# thunder.net
KiCad netlist of a schematic drawn in EAGLE
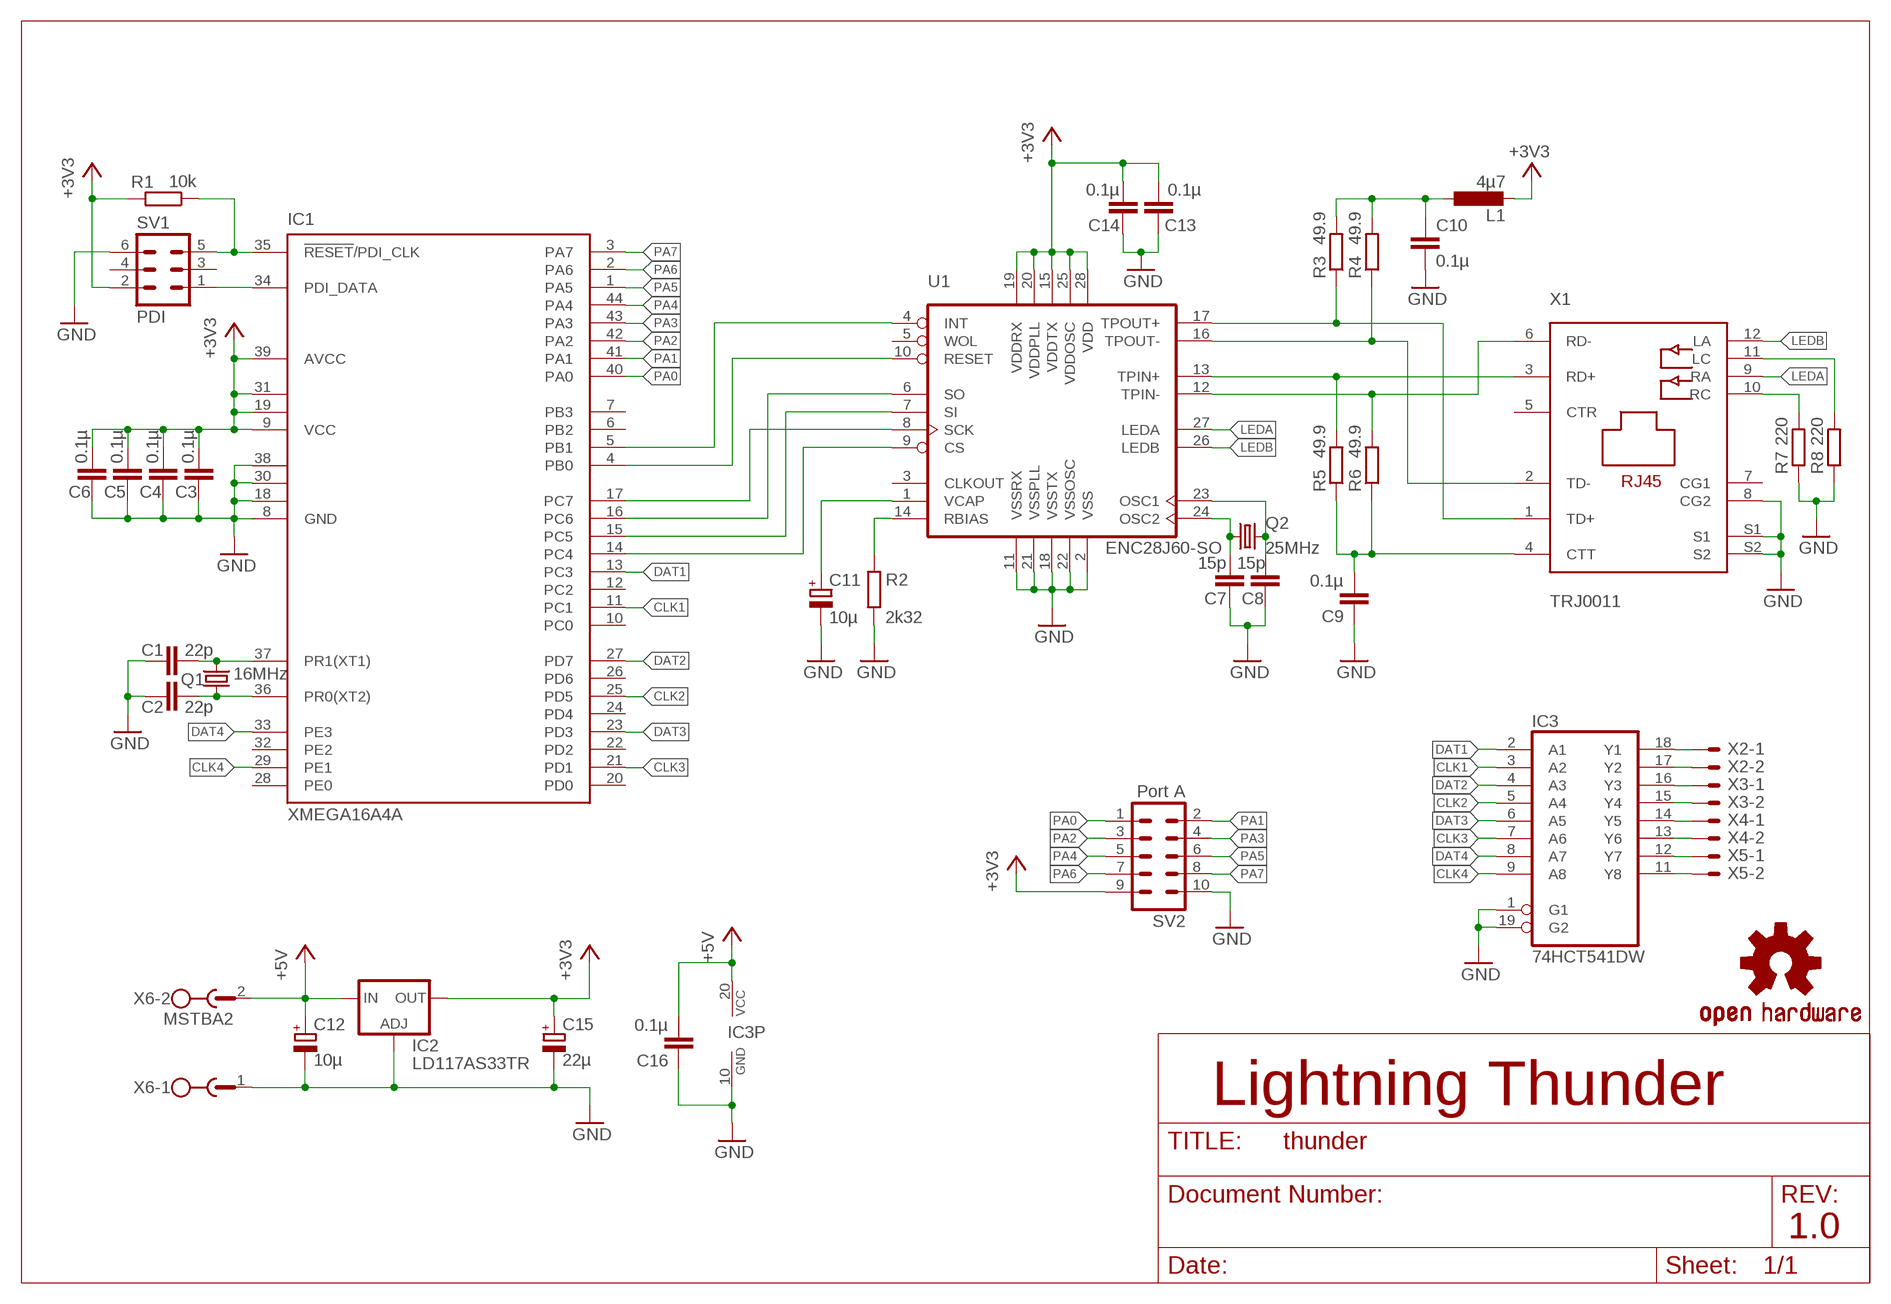
[diagram p0: schematic, sheet 1]

(export (version "E")
  (design (tool "Eeschema 10.0.6"))
  (components
    (comp (ref "C1")
      (value "22p")
      (footprint "eagle-import:C0805")
      (libsource (lib "eagle-import") (part "C-EUC0805"))
    )
    (comp (ref "C2")
      (value "22p")
      (footprint "eagle-import:C0805")
      (libsource (lib "eagle-import") (part "C-EUC0805"))
    )
    (comp (ref "C3")
      (value "0.1µ")
      (footprint "eagle-import:C0805")
      (libsource (lib "eagle-import") (part "C-EUC0805"))
    )
    (comp (ref "C4")
      (value "0.1µ")
      (footprint "eagle-import:C0805")
      (libsource (lib "eagle-import") (part "C-EUC0805"))
    )
    (comp (ref "C5")
      (value "0.1µ")
      (footprint "eagle-import:C0805")
      (libsource (lib "eagle-import") (part "C-EUC0805"))
    )
    (comp (ref "C6")
      (value "0.1µ")
      (footprint "eagle-import:C0805")
      (libsource (lib "eagle-import") (part "C-EUC0805"))
    )
    (comp (ref "C7")
      (value "15p")
      (footprint "eagle-import:C0805")
      (libsource (lib "eagle-import") (part "C-EUC0805"))
    )
    (comp (ref "C8")
      (value "15p")
      (footprint "eagle-import:C0805")
      (libsource (lib "eagle-import") (part "C-EUC0805"))
    )
    (comp (ref "C9")
      (value "0.1µ")
      (footprint "eagle-import:C0805")
      (libsource (lib "eagle-import") (part "C-EUC0805"))
    )
    (comp (ref "C10")
      (value "0.1µ")
      (footprint "eagle-import:C0805")
      (libsource (lib "eagle-import") (part "C-EUC0805"))
    )
    (comp (ref "C11")
      (value "10µ")
      (footprint "eagle-import:B_3528-21R")
      (libsource (lib "eagle-import") (part "CPOL-EUB/3528-21R"))
    )
    (comp (ref "C12")
      (value "10µ")
      (footprint "eagle-import:B_3528-21R")
      (libsource (lib "eagle-import") (part "CPOL-EUB/3528-21R"))
    )
    (comp (ref "C13")
      (value "0.1µ")
      (footprint "eagle-import:C0805")
      (libsource (lib "eagle-import") (part "C-EUC0805"))
    )
    (comp (ref "C14")
      (value "0.1µ")
      (footprint "eagle-import:C0805")
      (libsource (lib "eagle-import") (part "C-EUC0805"))
    )
    (comp (ref "C15")
      (value "22µ")
      (footprint "eagle-import:B_3528-21R")
      (libsource (lib "eagle-import") (part "CPOL-EUB/3528-21R"))
    )
    (comp (ref "C16")
      (value "0.1µ")
      (footprint "eagle-import:C0805")
      (libsource (lib "eagle-import") (part "C-EUC0805"))
    )
    (comp (ref "IC1")
      (value "XMEGA16A4A")
      (footprint "eagle-import:TQFP44")
      (libsource (lib "eagle-import") (part "XMEGA16A4A"))
    )
    (comp (ref "IC2")
      (value "LD117AS33TR")
      (footprint "eagle-import:SOT223")
      (libsource (lib "eagle-import") (part "LD117A?S33TR"))
    )
    (comp (ref "IC3")
      (value "74HCT541DW")
      (footprint "eagle-import:SO20W")
      (libsource (lib "eagle-import") (part "74541DWHCT"))
    )
    (comp (ref "L1")
      (value "4µ7")
      (footprint "eagle-import:L3225M")
      (libsource (lib "eagle-import") (part "L-EUL3225M"))
    )
    (comp (ref "LOGO1")
      (value "OSHW-LOGOS")
      (footprint "eagle-import:OSHW-LOGO-S")
      (libsource (lib "eagle-import") (part "OSHW-LOGOS"))
    )
    (comp (ref "Q1")
      (value "16MHz")
      (footprint "eagle-import:HC49U-V")
      (libsource (lib "eagle-import") (part "CRYSTALHC49U-V"))
    )
    (comp (ref "Q2")
      (value "25MHz")
      (footprint "eagle-import:HC49U-V")
      (libsource (lib "eagle-import") (part "CRYSTALHC49U-V"))
    )
    (comp (ref "R1")
      (value "10k")
      (footprint "eagle-import:R0805")
      (libsource (lib "eagle-import") (part "R-EU_R0805"))
    )
    (comp (ref "R2")
      (value "2k32")
      (footprint "eagle-import:R0805")
      (libsource (lib "eagle-import") (part "R-EU_R0805"))
    )
    (comp (ref "R3")
      (value "49.9")
      (footprint "eagle-import:R0805")
      (libsource (lib "eagle-import") (part "R-EU_R0805"))
    )
    (comp (ref "R4")
      (value "49.9")
      (footprint "eagle-import:R0805")
      (libsource (lib "eagle-import") (part "R-EU_R0805"))
    )
    (comp (ref "R5")
      (value "49.9")
      (footprint "eagle-import:R0805")
      (libsource (lib "eagle-import") (part "R-EU_R0805"))
    )
    (comp (ref "R6")
      (value "49.9")
      (footprint "eagle-import:R0805")
      (libsource (lib "eagle-import") (part "R-EU_R0805"))
    )
    (comp (ref "R7")
      (value "220")
      (footprint "eagle-import:R0805")
      (libsource (lib "eagle-import") (part "R-EU_R0805"))
    )
    (comp (ref "R8")
      (value "220")
      (footprint "eagle-import:R0805")
      (libsource (lib "eagle-import") (part "R-EU_R0805"))
    )
    (comp (ref "SV1")
      (value "PDI")
      (footprint "eagle-import:ML6")
      (libsource (lib "eagle-import") (part "ML6"))
    )
    (comp (ref "SV2")
      (value "Port A")
      (footprint "eagle-import:MA05-2")
      (libsource (lib "eagle-import") (part "MA05-2"))
    )
    (comp (ref "U1")
      (value "ENC28J60-SO")
      (footprint "eagle-import:SO28W")
      (libsource (lib "eagle-import") (part "ENC28J60-SO"))
    )
    (comp (ref "X1")
      (value "TRJ0011")
      (footprint "eagle-import:TRJ0011")
      (libsource (lib "eagle-import") (part "TRJ0011"))
    )
    (comp (ref "X2")
      (value "AKL18X-02W")
      (footprint "eagle-import:AKL182-02")
      (libsource (lib "eagle-import") (part "AKL18X-02W"))
    )
    (comp (ref "X3")
      (value "AKL18X-02W")
      (footprint "eagle-import:AKL182-02")
      (libsource (lib "eagle-import") (part "AKL18X-02W"))
    )
    (comp (ref "X4")
      (value "AKL18X-02W")
      (footprint "eagle-import:AKL182-02")
      (libsource (lib "eagle-import") (part "AKL18X-02W"))
    )
    (comp (ref "X5")
      (value "AKL18X-02W")
      (footprint "eagle-import:AKL182-02")
      (libsource (lib "eagle-import") (part "AKL18X-02W"))
    )
    (comp (ref "X6")
      (value "MSTBA2")
      (footprint "eagle-import:MSTBA2")
      (fields (field (name "MF") "FARNELL") (field (name "MPN") "1757242"))
      (libsource (lib "eagle-import") (part "MSTBA2"))
    )
  )
  (nets
    (net (code "1") (name "+3V3") (class "Default")
      (node (ref "C13") (pin "2") (pinfunction "2_2") (pintype "passive"))
      (node (ref "C14") (pin "2") (pinfunction "2_2") (pintype "passive"))
      (node (ref "C15") (pin "+") (pinfunction "+_+") (pintype "passive"))
      (node (ref "C3") (pin "2") (pinfunction "2_2") (pintype "passive"))
      (node (ref "C4") (pin "2") (pinfunction "2_2") (pintype "passive"))
      (node (ref "C5") (pin "2") (pinfunction "2_2") (pintype "passive"))
      (node (ref "C6") (pin "2") (pinfunction "2_2") (pintype "passive"))
      (node (ref "IC1") (pin "19") (pinfunction "VCC1_19") (pintype "power_in"))
      (node (ref "IC1") (pin "31") (pinfunction "VCC2_31") (pintype "power_in"))
      (node (ref "IC1") (pin "39") (pinfunction "AVCC_39") (pintype "power_in"))
      (node (ref "IC1") (pin "9") (pinfunction "VCC_9") (pintype "power_in"))
      (node (ref "IC2") (pin "4") (pinfunction "OUT_4") (pintype "passive"))
      (node (ref "L1") (pin "2") (pinfunction "2_2") (pintype "passive"))
      (node (ref "R1") (pin "2") (pinfunction "2_2") (pintype "passive"))
      (node (ref "SV1") (pin "2") (pinfunction "2_2") (pintype "passive"))
      (node (ref "SV2") (pin "9") (pinfunction "9_9") (pintype "passive"))
      (node (ref "U1") (pin "15") (pinfunction "VDDTX_15") (pintype "power_in"))
      (node (ref "U1") (pin "19") (pinfunction "VDDRX_19") (pintype "power_in"))
      (node (ref "U1") (pin "20") (pinfunction "VDDPLL_20") (pintype "power_in"))
      (node (ref "U1") (pin "25") (pinfunction "VDDOSC_25") (pintype "power_in"))
      (node (ref "U1") (pin "28") (pinfunction "VDD_28") (pintype "power_in"))
    )
    (net (code "2") (name "+5V") (class "Default")
      (node (ref "C12") (pin "+") (pinfunction "+_+") (pintype "passive"))
      (node (ref "C16") (pin "2") (pinfunction "2_2") (pintype "passive"))
      (node (ref "IC2") (pin "3") (pinfunction "IN_3") (pintype "input"))
      (node (ref "IC3") (pin "20") (pinfunction "VCC_20") (pintype "power_in"))
      (node (ref "X6") (pin "2") (pinfunction "1_2") (pintype "passive"))
    )
    (net (code "3") (name "CLK1") (class "Default")
      (node (ref "IC1") (pin "11") (pinfunction "PC1_11") (pintype "bidirectional"))
      (node (ref "IC3") (pin "3") (pinfunction "A2_3") (pintype "input"))
    )
    (net (code "4") (name "CLK2") (class "Default")
      (node (ref "IC1") (pin "25") (pinfunction "PD5_25") (pintype "bidirectional"))
      (node (ref "IC3") (pin "5") (pinfunction "A4_5") (pintype "input"))
    )
    (net (code "5") (name "CLK3") (class "Default")
      (node (ref "IC1") (pin "21") (pinfunction "PD1_21") (pintype "bidirectional"))
      (node (ref "IC3") (pin "7") (pinfunction "A6_7") (pintype "input"))
    )
    (net (code "6") (name "CLK4") (class "Default")
      (node (ref "IC1") (pin "29") (pinfunction "PE1_29") (pintype "bidirectional"))
      (node (ref "IC3") (pin "9") (pinfunction "A8_9") (pintype "input"))
    )
    (net (code "7") (name "DAT1") (class "Default")
      (node (ref "IC1") (pin "13") (pinfunction "PC3_13") (pintype "bidirectional"))
      (node (ref "IC3") (pin "2") (pinfunction "A1_2") (pintype "input"))
    )
    (net (code "8") (name "DAT2") (class "Default")
      (node (ref "IC1") (pin "27") (pinfunction "PD7_27") (pintype "bidirectional"))
      (node (ref "IC3") (pin "4") (pinfunction "A3_4") (pintype "input"))
    )
    (net (code "9") (name "DAT3") (class "Default")
      (node (ref "IC1") (pin "23") (pinfunction "PD3_23") (pintype "bidirectional"))
      (node (ref "IC3") (pin "6") (pinfunction "A5_6") (pintype "input"))
    )
    (net (code "10") (name "DAT4") (class "Default")
      (node (ref "IC1") (pin "33") (pinfunction "PE3_33") (pintype "bidirectional"))
      (node (ref "IC3") (pin "8") (pinfunction "A7_8") (pintype "input"))
    )
    (net (code "11") (name "GND") (class "Default")
      (node (ref "C1") (pin "1") (pinfunction "1_1") (pintype "passive"))
      (node (ref "C10") (pin "2") (pinfunction "2_2") (pintype "passive"))
      (node (ref "C11") (pin "-") (pinfunction "-_-") (pintype "passive"))
      (node (ref "C12") (pin "-") (pinfunction "-_-") (pintype "passive"))
      (node (ref "C13") (pin "1") (pinfunction "1_1") (pintype "passive"))
      (node (ref "C14") (pin "1") (pinfunction "1_1") (pintype "passive"))
      (node (ref "C15") (pin "-") (pinfunction "-_-") (pintype "passive"))
      (node (ref "C16") (pin "1") (pinfunction "1_1") (pintype "passive"))
      (node (ref "C2") (pin "1") (pinfunction "1_1") (pintype "passive"))
      (node (ref "C3") (pin "1") (pinfunction "1_1") (pintype "passive"))
      (node (ref "C4") (pin "1") (pinfunction "1_1") (pintype "passive"))
      (node (ref "C5") (pin "1") (pinfunction "1_1") (pintype "passive"))
      (node (ref "C6") (pin "1") (pinfunction "1_1") (pintype "passive"))
      (node (ref "C7") (pin "1") (pinfunction "1_1") (pintype "passive"))
      (node (ref "C8") (pin "1") (pinfunction "1_1") (pintype "passive"))
      (node (ref "C9") (pin "1") (pinfunction "1_1") (pintype "passive"))
      (node (ref "IC1") (pin "18") (pinfunction "GND1_18") (pintype "power_in"))
      (node (ref "IC1") (pin "30") (pinfunction "GND2_30") (pintype "power_in"))
      (node (ref "IC1") (pin "38") (pinfunction "GND3_38") (pintype "power_in"))
      (node (ref "IC1") (pin "8") (pinfunction "GND_8") (pintype "power_in"))
      (node (ref "IC2") (pin "1") (pinfunction "ADJ_1") (pintype "input"))
      (node (ref "IC3") (pin "1") (pinfunction "G1_1") (pintype "input"))
      (node (ref "IC3") (pin "10") (pinfunction "GND_10") (pintype "power_in"))
      (node (ref "IC3") (pin "19") (pinfunction "G2_19") (pintype "input"))
      (node (ref "R2") (pin "1") (pinfunction "1_1") (pintype "passive"))
      (node (ref "R7") (pin "1") (pinfunction "1_1") (pintype "passive"))
      (node (ref "R8") (pin "1") (pinfunction "1_1") (pintype "passive"))
      (node (ref "SV1") (pin "6") (pinfunction "6_6") (pintype "passive"))
      (node (ref "SV2") (pin "10") (pinfunction "10_10") (pintype "passive"))
      (node (ref "U1") (pin "11") (pinfunction "VSSRX_11") (pintype "power_in"))
      (node (ref "U1") (pin "18") (pinfunction "VSSTX_18") (pintype "power_in"))
      (node (ref "U1") (pin "2") (pinfunction "VSS_2") (pintype "power_in"))
      (node (ref "U1") (pin "21") (pinfunction "VSSPLL_21") (pintype "power_in"))
      (node (ref "U1") (pin "22") (pinfunction "VSSOSC_22") (pintype "power_in"))
      (node (ref "X1") (pin "8") (pinfunction "CG2_8") (pintype "passive"))
      (node (ref "X1") (pin "S1") (pinfunction "S1_S1") (pintype "passive"))
      (node (ref "X1") (pin "S2") (pinfunction "S2_S2") (pintype "passive"))
      (node (ref "X6") (pin "1") (pinfunction "1_1") (pintype "passive"))
    )
    (net (code "12") (name "LEDA") (class "Default")
      (node (ref "U1") (pin "27") (pinfunction "LEDA_27") (pintype "output"))
      (node (ref "X1") (pin "9") (pinfunction "RA_9") (pintype "passive"))
    )
    (net (code "13") (name "LEDB") (class "Default")
      (node (ref "U1") (pin "26") (pinfunction "LEDB_26") (pintype "output"))
      (node (ref "X1") (pin "12") (pinfunction "LA_12") (pintype "passive"))
    )
    (net (code "14") (name "Net-(C10-Pad1)") (class "Default")
      (node (ref "C10") (pin "1") (pinfunction "1_1") (pintype "passive"))
      (node (ref "L1") (pin "1") (pinfunction "1_1") (pintype "passive"))
      (node (ref "R3") (pin "2") (pinfunction "2_2") (pintype "passive"))
      (node (ref "R4") (pin "2") (pinfunction "2_2") (pintype "passive"))
    )
    (net (code "15") (name "Net-(IC1-PB0)") (class "Default")
      (node (ref "IC1") (pin "4") (pinfunction "PB0_4") (pintype "bidirectional"))
      (node (ref "U1") (pin "10") (pinfunction "RESET_10") (pintype "input"))
    )
    (net (code "16") (name "Net-(IC1-PB1)") (class "Default")
      (node (ref "IC1") (pin "5") (pinfunction "PB1_5") (pintype "bidirectional"))
      (node (ref "U1") (pin "4") (pinfunction "INT_4") (pintype "output"))
    )
    (net (code "17") (name "Net-(IC1-PC4)") (class "Default")
      (node (ref "IC1") (pin "14") (pinfunction "PC4_14") (pintype "bidirectional"))
      (node (ref "U1") (pin "9") (pinfunction "CS_9") (pintype "input"))
    )
    (net (code "18") (name "Net-(IC1-PC5)") (class "Default")
      (node (ref "IC1") (pin "15") (pinfunction "PC5_15") (pintype "bidirectional"))
      (node (ref "U1") (pin "7") (pinfunction "SI_7") (pintype "input"))
    )
    (net (code "19") (name "Net-(IC1-PC6)") (class "Default")
      (node (ref "IC1") (pin "16") (pinfunction "PC6_16") (pintype "bidirectional"))
      (node (ref "U1") (pin "6") (pinfunction "SO_6") (pintype "open_collector"))
    )
    (net (code "20") (name "Net-(IC1-PC7)") (class "Default")
      (node (ref "IC1") (pin "17") (pinfunction "PC7_17") (pintype "bidirectional"))
      (node (ref "U1") (pin "8") (pinfunction "SCK_8") (pintype "input"))
    )
    (net (code "21") (name "Net-(IC1-PDI_DATA)") (class "Default")
      (node (ref "IC1") (pin "34") (pinfunction "PDI_DATA_34") (pintype "bidirectional"))
      (node (ref "SV1") (pin "1") (pinfunction "1_1") (pintype "passive"))
    )
    (net (code "22") (name "Net-(IC1-PR0(XT2))") (class "Default")
      (node (ref "C2") (pin "2") (pinfunction "2_2") (pintype "passive"))
      (node (ref "IC1") (pin "36") (pinfunction "PR0(XT2)_36") (pintype "bidirectional"))
      (node (ref "Q1") (pin "1") (pinfunction "1_1") (pintype "passive"))
    )
    (net (code "23") (name "Net-(IC1-PR1(XT1))") (class "Default")
      (node (ref "C1") (pin "2") (pinfunction "2_2") (pintype "passive"))
      (node (ref "IC1") (pin "37") (pinfunction "PR1(XT1)_37") (pintype "bidirectional"))
      (node (ref "Q1") (pin "2") (pinfunction "2_2") (pintype "passive"))
    )
    (net (code "24") (name "Net-(IC1-~{RESET}{slash}PDI_CLK)") (class "Default")
      (node (ref "IC1") (pin "35") (pinfunction "~{RESET}/PDI_CLK_35") (pintype "bidirectional"))
      (node (ref "R1") (pin "1") (pinfunction "1_1") (pintype "passive"))
      (node (ref "SV1") (pin "5") (pinfunction "5_5") (pintype "passive"))
    )
    (net (code "25") (name "Net-(IC3A-Y1)") (class "Default")
      (node (ref "IC3") (pin "18") (pinfunction "Y1_18") (pintype "tri_state"))
      (node (ref "X2") (pin "P$1") (pinfunction "S_P$1") (pintype "passive"))
    )
    (net (code "26") (name "Net-(IC3A-Y2)") (class "Default")
      (node (ref "IC3") (pin "17") (pinfunction "Y2_17") (pintype "tri_state"))
      (node (ref "X2") (pin "P$2") (pinfunction "S_P$2") (pintype "passive"))
    )
    (net (code "27") (name "Net-(IC3A-Y3)") (class "Default")
      (node (ref "IC3") (pin "16") (pinfunction "Y3_16") (pintype "tri_state"))
      (node (ref "X3") (pin "P$1") (pinfunction "S_P$1") (pintype "passive"))
    )
    (net (code "28") (name "Net-(IC3A-Y4)") (class "Default")
      (node (ref "IC3") (pin "15") (pinfunction "Y4_15") (pintype "tri_state"))
      (node (ref "X3") (pin "P$2") (pinfunction "S_P$2") (pintype "passive"))
    )
    (net (code "29") (name "Net-(IC3A-Y5)") (class "Default")
      (node (ref "IC3") (pin "14") (pinfunction "Y5_14") (pintype "tri_state"))
      (node (ref "X4") (pin "P$1") (pinfunction "S_P$1") (pintype "passive"))
    )
    (net (code "30") (name "Net-(IC3A-Y6)") (class "Default")
      (node (ref "IC3") (pin "13") (pinfunction "Y6_13") (pintype "tri_state"))
      (node (ref "X4") (pin "P$2") (pinfunction "S_P$2") (pintype "passive"))
    )
    (net (code "31") (name "Net-(IC3A-Y7)") (class "Default")
      (node (ref "IC3") (pin "12") (pinfunction "Y7_12") (pintype "tri_state"))
      (node (ref "X5") (pin "P$1") (pinfunction "S_P$1") (pintype "passive"))
    )
    (net (code "32") (name "Net-(IC3A-Y8)") (class "Default")
      (node (ref "IC3") (pin "11") (pinfunction "Y8_11") (pintype "tri_state"))
      (node (ref "X5") (pin "P$2") (pinfunction "S_P$2") (pintype "passive"))
    )
    (net (code "33") (name "Net-(U1-OSC1)") (class "Default")
      (node (ref "C8") (pin "2") (pinfunction "2_2") (pintype "passive"))
      (node (ref "Q2") (pin "2") (pinfunction "2_2") (pintype "passive"))
      (node (ref "U1") (pin "23") (pinfunction "OSC1_23") (pintype "input"))
    )
    (net (code "34") (name "Net-(U1-OSC2)") (class "Default")
      (node (ref "C7") (pin "2") (pinfunction "2_2") (pintype "passive"))
      (node (ref "Q2") (pin "1") (pinfunction "1_1") (pintype "passive"))
      (node (ref "U1") (pin "24") (pinfunction "OSC2_24") (pintype "output"))
    )
    (net (code "35") (name "Net-(U1-RBIAS)") (class "Default")
      (node (ref "R2") (pin "2") (pinfunction "2_2") (pintype "passive"))
      (node (ref "U1") (pin "14") (pinfunction "RBIAS_14") (pintype "passive"))
    )
    (net (code "36") (name "Net-(U1-TPIN+)") (class "Default")
      (node (ref "R5") (pin "2") (pinfunction "2_2") (pintype "passive"))
      (node (ref "U1") (pin "13") (pinfunction "TPIN+_13") (pintype "input"))
      (node (ref "X1") (pin "3") (pinfunction "RD+_3") (pintype "passive"))
    )
    (net (code "37") (name "Net-(U1-TPIN-)") (class "Default")
      (node (ref "R6") (pin "2") (pinfunction "2_2") (pintype "passive"))
      (node (ref "U1") (pin "12") (pinfunction "TPIN-_12") (pintype "input"))
      (node (ref "X1") (pin "6") (pinfunction "RD-_6") (pintype "passive"))
    )
    (net (code "38") (name "Net-(U1-TPOUT+)") (class "Default")
      (node (ref "R3") (pin "1") (pinfunction "1_1") (pintype "passive"))
      (node (ref "U1") (pin "17") (pinfunction "TPOUT+_17") (pintype "output"))
      (node (ref "X1") (pin "1") (pinfunction "TD+_1") (pintype "passive"))
    )
    (net (code "39") (name "Net-(U1-TPOUT-)") (class "Default")
      (node (ref "R4") (pin "1") (pinfunction "1_1") (pintype "passive"))
      (node (ref "U1") (pin "16") (pinfunction "TPOUT-_16") (pintype "output"))
      (node (ref "X1") (pin "2") (pinfunction "TD-_2") (pintype "passive"))
    )
    (net (code "40") (name "Net-(U1-VCAP)") (class "Default")
      (node (ref "C11") (pin "+") (pinfunction "+_+") (pintype "passive"))
      (node (ref "U1") (pin "1") (pinfunction "VCAP_1") (pintype "power_in"))
    )
    (net (code "41") (name "Net-(X1-CTT)") (class "Default")
      (node (ref "C9") (pin "2") (pinfunction "2_2") (pintype "passive"))
      (node (ref "R5") (pin "1") (pinfunction "1_1") (pintype "passive"))
      (node (ref "R6") (pin "1") (pinfunction "1_1") (pintype "passive"))
      (node (ref "X1") (pin "4") (pinfunction "CTT_4") (pintype "passive"))
    )
    (net (code "42") (name "Net-(X1-LC)") (class "Default")
      (node (ref "R8") (pin "2") (pinfunction "2_2") (pintype "passive"))
      (node (ref "X1") (pin "11") (pinfunction "LC_11") (pintype "passive"))
    )
    (net (code "43") (name "Net-(X1-RC)") (class "Default")
      (node (ref "R7") (pin "2") (pinfunction "2_2") (pintype "passive"))
      (node (ref "X1") (pin "10") (pinfunction "RC_10") (pintype "passive"))
    )
    (net (code "44") (name "PA0") (class "Default")
      (node (ref "IC1") (pin "40") (pinfunction "PA0_40") (pintype "bidirectional"))
      (node (ref "SV2") (pin "1") (pinfunction "1_1") (pintype "passive"))
    )
    (net (code "45") (name "PA1") (class "Default")
      (node (ref "IC1") (pin "41") (pinfunction "PA1_41") (pintype "bidirectional"))
      (node (ref "SV2") (pin "2") (pinfunction "2_2") (pintype "passive"))
    )
    (net (code "46") (name "PA2") (class "Default")
      (node (ref "IC1") (pin "42") (pinfunction "PA2_42") (pintype "bidirectional"))
      (node (ref "SV2") (pin "3") (pinfunction "3_3") (pintype "passive"))
    )
    (net (code "47") (name "PA3") (class "Default")
      (node (ref "IC1") (pin "43") (pinfunction "PA3_43") (pintype "bidirectional"))
      (node (ref "SV2") (pin "4") (pinfunction "4_4") (pintype "passive"))
    )
    (net (code "48") (name "PA4") (class "Default")
      (node (ref "IC1") (pin "44") (pinfunction "PA4_44") (pintype "bidirectional"))
      (node (ref "SV2") (pin "5") (pinfunction "5_5") (pintype "passive"))
    )
    (net (code "49") (name "PA5") (class "Default")
      (node (ref "IC1") (pin "1") (pinfunction "PA5_1") (pintype "bidirectional"))
      (node (ref "SV2") (pin "6") (pinfunction "6_6") (pintype "passive"))
    )
    (net (code "50") (name "PA6") (class "Default")
      (node (ref "IC1") (pin "2") (pinfunction "PA6_2") (pintype "bidirectional"))
      (node (ref "SV2") (pin "7") (pinfunction "7_7") (pintype "passive"))
    )
    (net (code "51") (name "PA7") (class "Default")
      (node (ref "IC1") (pin "3") (pinfunction "PA7_3") (pintype "bidirectional"))
      (node (ref "SV2") (pin "8") (pinfunction "8_8") (pintype "passive"))
    )
    (net (code "52") (name "unconnected-(IC1-PB2-Pad6)") (class "Default")
      (node (ref "IC1") (pin "6") (pinfunction "PB2_6") (pintype "bidirectional"))
    )
    (net (code "53") (name "unconnected-(IC1-PB3-Pad7)") (class "Default")
      (node (ref "IC1") (pin "7") (pinfunction "PB3_7") (pintype "bidirectional"))
    )
    (net (code "54") (name "unconnected-(IC1-PC0-Pad10)") (class "Default")
      (node (ref "IC1") (pin "10") (pinfunction "PC0_10") (pintype "bidirectional"))
    )
    (net (code "55") (name "unconnected-(IC1-PC2-Pad12)") (class "Default")
      (node (ref "IC1") (pin "12") (pinfunction "PC2_12") (pintype "bidirectional"))
    )
    (net (code "56") (name "unconnected-(IC1-PD0-Pad20)") (class "Default")
      (node (ref "IC1") (pin "20") (pinfunction "PD0_20") (pintype "bidirectional"))
    )
    (net (code "57") (name "unconnected-(IC1-PD2-Pad22)") (class "Default")
      (node (ref "IC1") (pin "22") (pinfunction "PD2_22") (pintype "bidirectional"))
    )
    (net (code "58") (name "unconnected-(IC1-PD4-Pad24)") (class "Default")
      (node (ref "IC1") (pin "24") (pinfunction "PD4_24") (pintype "bidirectional"))
    )
    (net (code "59") (name "unconnected-(IC1-PD6-Pad26)") (class "Default")
      (node (ref "IC1") (pin "26") (pinfunction "PD6_26") (pintype "bidirectional"))
    )
    (net (code "60") (name "unconnected-(IC1-PE0-Pad28)") (class "Default")
      (node (ref "IC1") (pin "28") (pinfunction "PE0_28") (pintype "bidirectional"))
    )
    (net (code "61") (name "unconnected-(IC1-PE2-Pad32)") (class "Default")
      (node (ref "IC1") (pin "32") (pinfunction "PE2_32") (pintype "bidirectional"))
    )
    (net (code "62") (name "unconnected-(SV1-Pad3)") (class "Default")
      (node (ref "SV1") (pin "3") (pinfunction "3_3") (pintype "passive"))
    )
    (net (code "63") (name "unconnected-(SV1-Pad4)") (class "Default")
      (node (ref "SV1") (pin "4") (pinfunction "4_4") (pintype "passive"))
    )
    (net (code "64") (name "unconnected-(U1-CLKOUT-Pad3)") (class "Default")
      (node (ref "U1") (pin "3") (pinfunction "CLKOUT_3") (pintype "output"))
    )
    (net (code "65") (name "unconnected-(U1-WOL-Pad5)") (class "Default")
      (node (ref "U1") (pin "5") (pinfunction "WOL_5") (pintype "output"))
    )
    (net (code "66") (name "unconnected-(X1-CG1-Pad7)") (class "Default")
      (node (ref "X1") (pin "7") (pinfunction "CG1_7") (pintype "passive"))
    )
    (net (code "67") (name "unconnected-(X1-CTR-Pad5)") (class "Default")
      (node (ref "X1") (pin "5") (pinfunction "CTR_5") (pintype "passive"))
    )
  )
)
